# Gyroscope.net
KiCad netlist of a schematic drawn in Altium Designer
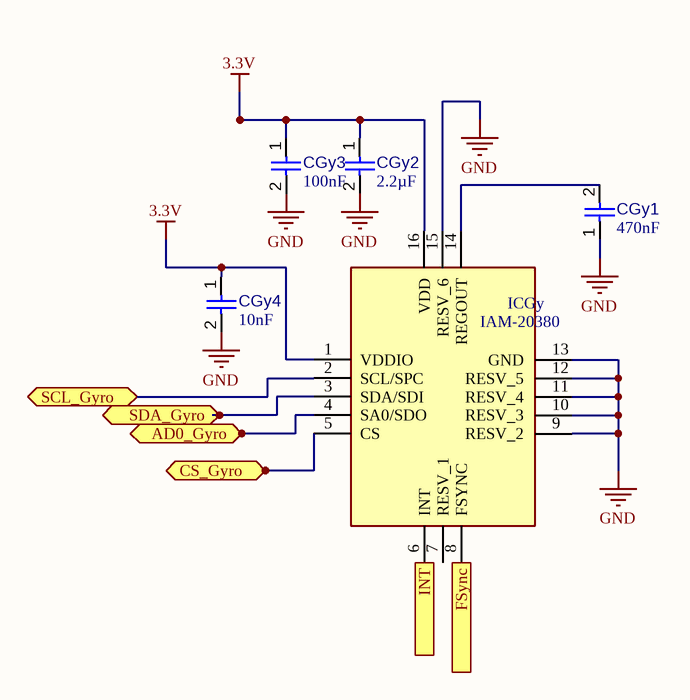
[diagram p0: Gyroscope.SchDoc]

(export (version "E")
  (design (tool "Eeschema 10.0.6"))
  (components
    (comp (ref "CGy1")
      (value "470nF")
      (footprint "CAPC0402(1005)60_L")
      (description "Chip Capacitor, 470nF +/-40%, 10V, 0402, Thickness 0.6 mm")
      (fields (field (name "TOLERANCE") "20%") (field (name "Comment") "Capacitor 470nF +/-40% 10V 0402"))
      (libsource (lib "Project Sunsat") (part "CAP-NP-2"))
    )
    (comp (ref "CGy2")
      (value "2.2µF")
      (footprint "CAPC0402(1005)60_L")
      (description "Chip Capacitor, 2,2µF +/-20%, 10V, 0402, Thickness 0.6 mm")
      (fields (field (name "TOLERANCE") "10%") (field (name "Comment") "Capacitor 2,2µF +/-20% 10V 0402"))
      (libsource (lib "Project Sunsat") (part "CAP-NP-2"))
    )
    (comp (ref "CGy3")
      (value "100nF")
      (footprint "CAPC1005X56X25LL10T15")
      (description "Chip Capacitor, 0.1 uF, +/- 5%, 16 V, 0402 (1005 Metric)")
      (fields (field (name "TOLERANCE") "5%") (field (name "Comment") "Capacitor 0.1 uF +/- 5% 16 V 0402"))
      (libsource (lib "Project Sunsat") (part "CAP-NP-2"))
    )
    (comp (ref "CGy4")
      (value "10nF")
      (footprint "CAPC0402(1005)60_L")
      (description "Chip Capacitor, 10nF +/-20%, 50V, 0402, Thickness 0.6 mm")
      (fields (field (name "TOLERANCE") "5%") (field (name "Comment") "Capacitor 10nF +/-20% 50V 0402"))
      (libsource (lib "Project Sunsat") (part "CAP-NP-2"))
    )
    (comp (ref "ICGy")
      (value "IAM-20380")
      (footprint "SamacSys:IAM20680HP")
      (description "Integrated Circuit")
      (fields (field (name "MOUSER PART NUMBER") "410-IAM-20380"))
      (libsource (lib "*") (part "IAM-20380"))
    )
  )
  (nets
    (net (code "1") (name "/AD0_Gyro") (class "Default")
      (node (ref "ICGy") (pin "4") (pinfunction "SA0/SDO_4") (pintype "passive"))
    )
    (net (code "2") (name "/CS_Gyro") (class "Default")
      (node (ref "ICGy") (pin "5") (pinfunction "CS_5") (pintype "passive"))
    )
    (net (code "3") (name "/FSync") (class "Default")
      (node (ref "ICGy") (pin "8") (pinfunction "FSYNC_8") (pintype "passive"))
    )
    (net (code "4") (name "/INT") (class "Default")
      (node (ref "ICGy") (pin "6") (pinfunction "INT_6") (pintype "passive"))
    )
    (net (code "5") (name "/SCL_Gyro") (class "Default")
      (node (ref "ICGy") (pin "2") (pinfunction "SCL/SPC_2") (pintype "passive"))
    )
    (net (code "6") (name "/SDA_Gyro") (class "Default")
      (node (ref "ICGy") (pin "3") (pinfunction "SDA/SDI_3") (pintype "passive"))
    )
    (net (code "7") (name "3.3V") (class "Default")
      (node (ref "CGy2") (pin "1") (pinfunction "1_1") (pintype "passive"))
      (node (ref "CGy3") (pin "1") (pinfunction "1_1") (pintype "passive"))
      (node (ref "CGy4") (pin "1") (pinfunction "1_1") (pintype "passive"))
      (node (ref "ICGy") (pin "1") (pinfunction "VDDIO_1") (pintype "passive"))
      (node (ref "ICGy") (pin "16") (pinfunction "VDD_16") (pintype "passive"))
    )
    (net (code "8") (name "GND") (class "Default")
      (node (ref "CGy1") (pin "1") (pinfunction "1_1") (pintype "passive"))
      (node (ref "CGy2") (pin "2") (pinfunction "2_2") (pintype "passive"))
      (node (ref "CGy3") (pin "2") (pinfunction "2_2") (pintype "passive"))
      (node (ref "CGy4") (pin "2") (pinfunction "2_2") (pintype "passive"))
      (node (ref "ICGy") (pin "10") (pinfunction "RESV_3_10") (pintype "passive"))
      (node (ref "ICGy") (pin "11") (pinfunction "RESV_4_11") (pintype "passive"))
      (node (ref "ICGy") (pin "12") (pinfunction "RESV_5_12") (pintype "passive"))
      (node (ref "ICGy") (pin "13") (pinfunction "GND_13") (pintype "passive"))
      (node (ref "ICGy") (pin "15") (pinfunction "RESV_6_15") (pintype "passive"))
      (node (ref "ICGy") (pin "9") (pinfunction "RESV_2_9") (pintype "passive"))
    )
    (net (code "9") (name "Net-(ICGy-REGOUT)") (class "Default")
      (node (ref "CGy1") (pin "2") (pinfunction "2_2") (pintype "passive"))
      (node (ref "ICGy") (pin "14") (pinfunction "REGOUT_14") (pintype "passive"))
    )
    (net (code "10") (name "unconnected-(ICGy-RESV_1-Pad7)") (class "Default")
      (node (ref "ICGy") (pin "7") (pinfunction "RESV_1_7") (pintype "passive"))
    )
  )
)
